# 2_MG32F003_TSSOP20.net
KiCad netlist of a schematic drawn in Altium Designer
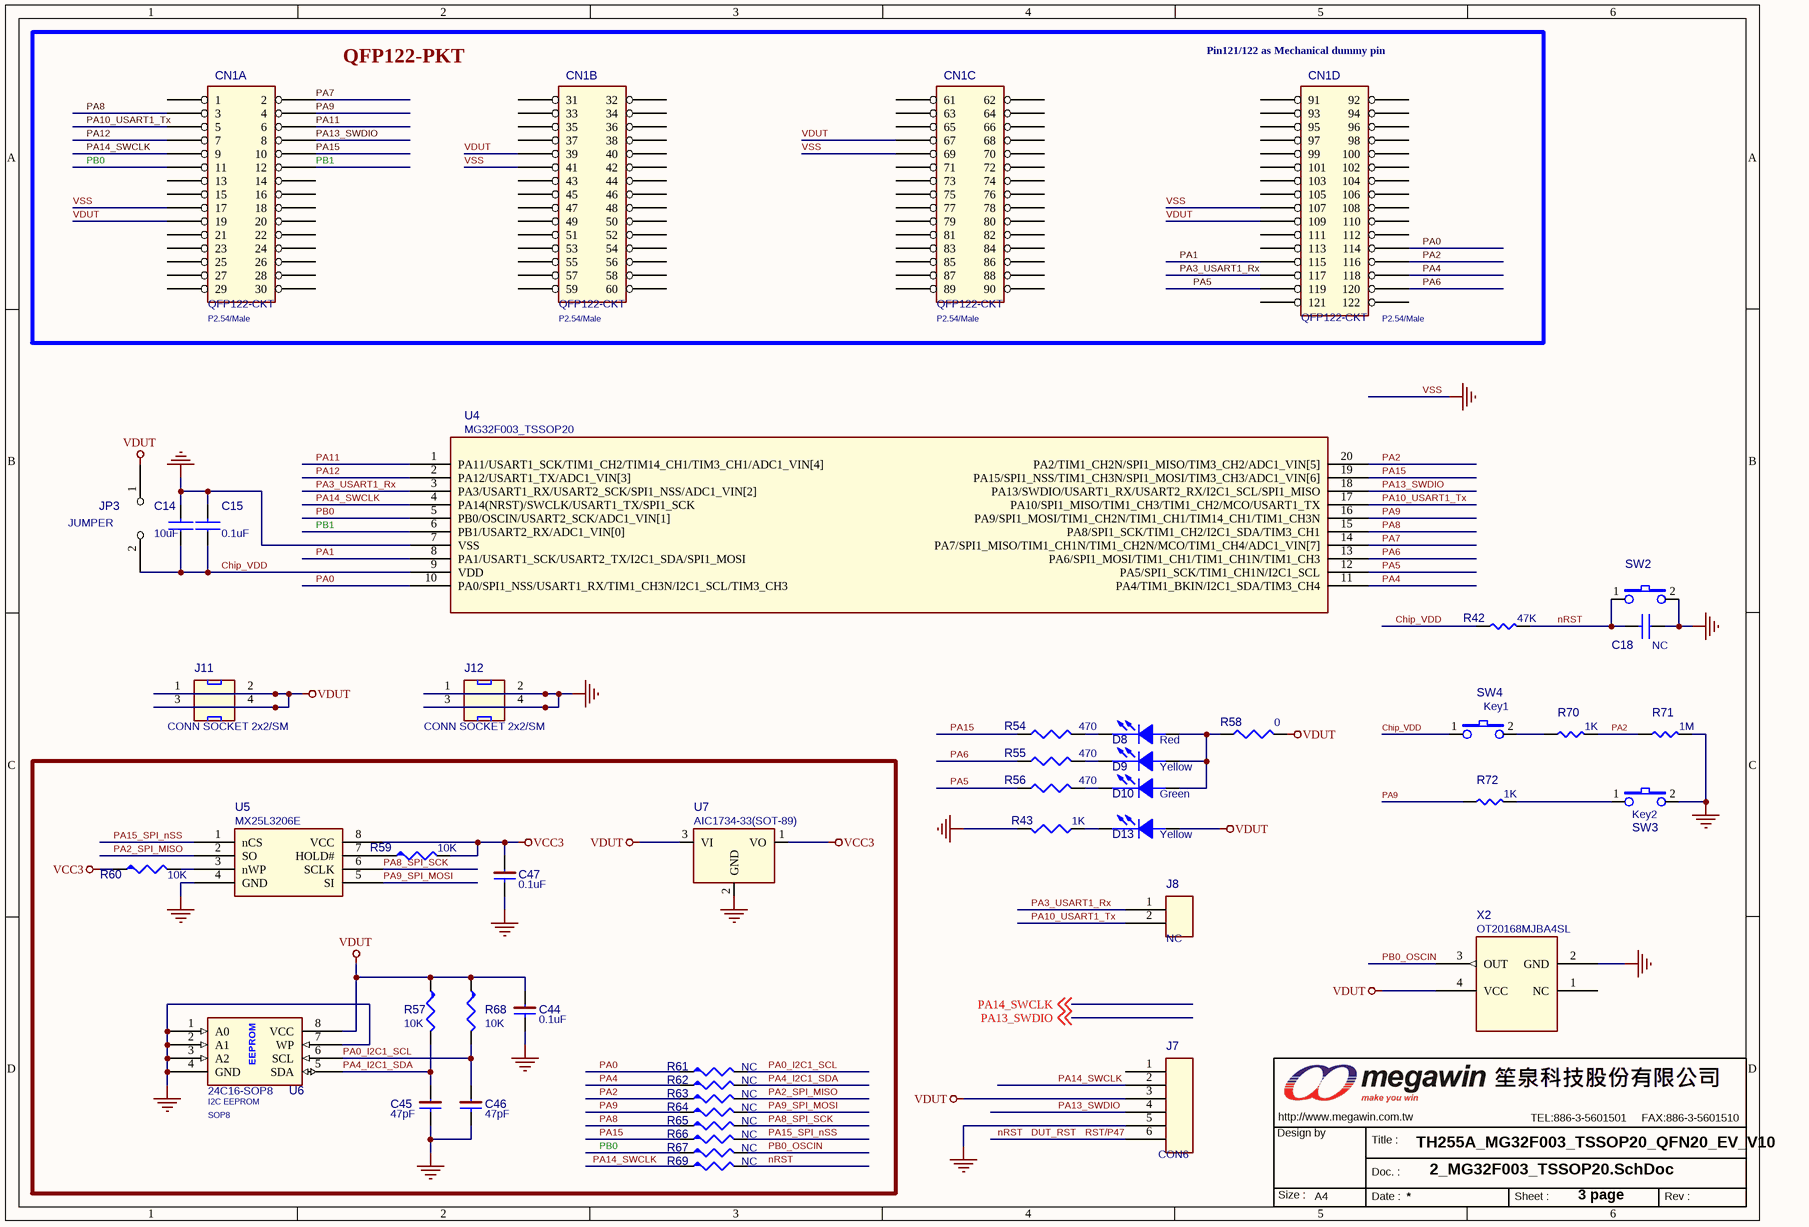
[diagram p0: 2_MG32F003_TSSOP20.SchDoc]

(export (version "E")
  (design (tool "Eeschema 10.0.6"))
  (components
    (comp (ref "C14") (value "10uF") (footprint "C-0603") (libsource (lib "*") (part "CAP NP_Dup1")))
    (comp (ref "C15") (value "0.1uF") (footprint "C-0603") (libsource (lib "*") (part "CAP NP_Dup1")))
    (comp (ref "C18") (value "NC") (footprint "C-0603") (libsource (lib "*") (part "CAP NP_Dup1")))
    (comp (ref "C44") (value "0.1uF") (footprint "C-0603") (libsource (lib "*") (part "CAP-NP")))
    (comp (ref "C45") (value "47pF") (footprint "C-0603") (libsource (lib "*") (part "CAP-NP")))
    (comp (ref "C46") (value "47pF") (footprint "C-0603") (libsource (lib "*") (part "CAP-NP")))
    (comp (ref "C47") (value "0.1uF") (footprint "C-0603") (libsource (lib "*") (part "CAP-NP")))
    (comp (ref "CN1")
      (value "QFP122-CKT")
      (footprint "QFP122-P2.54-CKT")
      (fields (field (name "PACKAGE") "P2.54/Male"))
      (libsource (lib "*") (part "QFP122-CKT"))
    )
    (comp (ref "D8") (value "Red") (libsource (lib "*") (part "LED")))
    (comp (ref "D9") (value "Yellow") (libsource (lib "*") (part "LED")))
    (comp (ref "D10") (value "Green") (libsource (lib "*") (part "LED")))
    (comp (ref "D13") (value "Yellow") (libsource (lib "*") (part "LED")))
    (comp (ref "J7") (value "CON6") (footprint "PS6P254") (libsource (lib "*") (part "CON6_Dup1")))
    (comp (ref "J8") (value "NC") (footprint "PS2P254") (libsource (lib "*") (part "CON2")))
    (comp (ref "J11")
      (value "CONN SOCKET 2x2/SM")
      (footprint "PS2X2P254")
      (libsource (lib "*") (part "CONN SOCKET 2x2/SM"))
    )
    (comp (ref "J12")
      (value "CONN SOCKET 2x2/SM")
      (footprint "PS2X2P254")
      (libsource (lib "*") (part "CONN SOCKET 2x2/SM"))
    )
    (comp (ref "JP3") (value "JUMPER") (footprint "PS2P254") (libsource (lib "*") (part "JUMPER")))
    (comp (ref "MW1")
      (value "MW-A4")
      (footprint "MEGAWIN_3.4")
      (fields
        (field (name "ORGADDR2") "http://www.megawin.com.tw")
        (field (name "ORGADDR3") "TEL:886-3-5601501     FAX:886-3-5601510")
      )
      (libsource (lib "201407_SCHLIB") (part "MW_A4_2"))
    )
    (comp (ref "R42") (value "47K") (footprint "R-0603") (libsource (lib "*") (part "R_Dup3")))
    (comp (ref "R43") (value "1K") (footprint "R-0603") (libsource (lib "*") (part "R_Dup4")))
    (comp (ref "R54") (value "470") (footprint "R-0603") (libsource (lib "*") (part "R_Dup4")))
    (comp (ref "R55") (value "470") (footprint "R-0603") (libsource (lib "*") (part "R_Dup4")))
    (comp (ref "R56") (value "470") (footprint "R-0603") (libsource (lib "*") (part "R_Dup4")))
    (comp (ref "R57") (value "10K") (footprint "R-0603") (libsource (lib "*") (part "R")))
    (comp (ref "R58") (value "0") (footprint "R-0603") (libsource (lib "*") (part "R_Dup4")))
    (comp (ref "R59") (value "10K") (footprint "R-0603") (libsource (lib "*") (part "R")))
    (comp (ref "R60") (value "10K") (footprint "R-0603") (libsource (lib "*") (part "R")))
    (comp (ref "R61") (value "NC") (footprint "R-0603") (libsource (lib "*") (part "R")))
    (comp (ref "R62") (value "NC") (footprint "R-0603") (libsource (lib "*") (part "R")))
    (comp (ref "R63") (value "NC") (footprint "R-0603") (libsource (lib "*") (part "R")))
    (comp (ref "R64") (value "NC") (footprint "R-0603") (libsource (lib "*") (part "R")))
    (comp (ref "R65") (value "NC") (footprint "R-0603") (libsource (lib "*") (part "R")))
    (comp (ref "R66") (value "NC") (footprint "R-0603") (libsource (lib "*") (part "R")))
    (comp (ref "R67") (value "NC") (footprint "R-0603") (libsource (lib "*") (part "R")))
    (comp (ref "R68") (value "10K") (footprint "R-0603") (libsource (lib "*") (part "R")))
    (comp (ref "R69") (value "NC") (footprint "R-0603") (libsource (lib "*") (part "R")))
    (comp (ref "R70") (value "1K") (footprint "R-0603") (libsource (lib "*") (part "R_Dup3")))
    (comp (ref "R71") (value "1M") (footprint "R-0603") (libsource (lib "*") (part "R_Dup3")))
    (comp (ref "R72") (value "1K") (footprint "R-0603") (libsource (lib "*") (part "R_Dup3")))
    (comp (ref "SW2")
      (value "SW TACT-SPST")
      (footprint "SW_T_2P")
      (libsource (lib "*") (part "SW TACT-SPST"))
    )
    (comp (ref "SW3") (value "Key2") (footprint "SW_T_2P") (libsource (lib "*") (part "SW TACT-SPST")))
    (comp (ref "SW4") (value "Key1") (footprint "SW_T_2P") (libsource (lib "*") (part "SW TACT-SPST")))
    (comp (ref "U4")
      (value "MG32F003_TSSOP20")
      (footprint "TSSOP20_170P065")
      (libsource (lib "*") (part "MG32F003_TSSOP20"))
    )
    (comp (ref "U5") (value "MX25L3206E") (footprint "SO8_208P127") (libsource (lib "*") (part "MX25L3206E")))
    (comp (ref "U6")
      (value "24C16-SOP8")
      (footprint "SO8_150P127")
      (fields (field (name "FUNCTION") "I2C EEPROM") (field (name "PACKAGE") "SOP8"))
      (libsource (lib "*") (part "ICM-24CXX"))
    )
    (comp (ref "U7") (value "AIC1734-33(SOT-89)") (libsource (lib "*") (part "AIC1722-33")))
    (comp (ref "X2")
      (value "OT20168MJBA4SL")
      (footprint "OSC_2.0X1.6_SMD")
      (libsource (lib "*") (part "OSC8_0"))
    )
  )
  (nets
    (net (code "1") (name "/Chip_VDD") (class "Default")
      (node (ref "C14") (pin "1") (pinfunction "1_1") (pintype "passive"))
      (node (ref "C15") (pin "1") (pinfunction "1_1") (pintype "passive"))
      (node (ref "JP3") (pin "2") (pinfunction "2_2") (pintype "passive"))
      (node (ref "R42") (pin "1") (pinfunction "1_1") (pintype "passive"))
      (node (ref "SW4") (pin "1") (pinfunction "1_1") (pintype "passive"))
      (node (ref "U4") (pin "9") (pinfunction "VDD_9") (pintype "passive"))
    )
    (net (code "2") (name "/DUT_RST") (class "Default")
      (node (ref "C18") (pin "2") (pinfunction "2_2") (pintype "passive"))
      (node (ref "J7") (pin "6") (pinfunction "6_6") (pintype "passive"))
      (node (ref "R42") (pin "2") (pinfunction "2_2") (pintype "passive"))
      (node (ref "R69") (pin "2") (pinfunction "2_2") (pintype "passive"))
      (node (ref "SW2") (pin "1") (pinfunction "1_1") (pintype "passive"))
    )
    (net (code "3") (name "/PA0") (class "Default")
      (node (ref "CN1") (pin "114") (pinfunction "114_114") (pintype "passive"))
      (node (ref "R61") (pin "1") (pinfunction "1_1") (pintype "passive"))
      (node (ref "U4") (pin "10") (pinfunction "PA0/SPI1_NSS/USART1_RX/TIM1_CH3N/I2C1_SCL/TIM3_CH3_10") (pintype "passive"))
    )
    (net (code "4") (name "/PA0_I2C1_SCL") (class "Default")
      (node (ref "C46") (pin "1") (pinfunction "1_1") (pintype "passive"))
      (node (ref "R61") (pin "2") (pinfunction "2_2") (pintype "passive"))
      (node (ref "R68") (pin "2") (pinfunction "2_2") (pintype "passive"))
      (node (ref "U6") (pin "6") (pinfunction "SCL_6") (pintype "input"))
    )
    (net (code "5") (name "/PA1") (class "Default")
      (node (ref "CN1") (pin "115") (pinfunction "115_115") (pintype "passive"))
      (node (ref "U4") (pin "8") (pinfunction "PA1/USART1_SCK/USART2_TX/I2C1_SDA/SPI1_MOSI_8") (pintype "passive"))
    )
    (net (code "6") (name "/PA2") (class "Default")
      (node (ref "CN1") (pin "116") (pinfunction "116_116") (pintype "passive"))
      (node (ref "R63") (pin "1") (pinfunction "1_1") (pintype "passive"))
      (node (ref "R70") (pin "2") (pinfunction "2_2") (pintype "passive"))
      (node (ref "R71") (pin "1") (pinfunction "1_1") (pintype "passive"))
      (node (ref "U4") (pin "20") (pinfunction "PA2/TIM1_CH2N/SPI1_MISO/TIM3_CH2/ADC1_VIN[5]_20") (pintype "passive"))
    )
    (net (code "7") (name "/PA2_SPI_MISO") (class "Default")
      (node (ref "R63") (pin "2") (pinfunction "2_2") (pintype "passive"))
      (node (ref "U5") (pin "2") (pinfunction "SO_2") (pintype "passive"))
    )
    (net (code "8") (name "/PA3_USART1_Rx") (class "Default")
      (node (ref "CN1") (pin "117") (pinfunction "117_117") (pintype "passive"))
      (node (ref "J8") (pin "1") (pinfunction "1_1") (pintype "passive"))
      (node (ref "U4") (pin "3") (pinfunction "PA3/USART1_RX/USART2_SCK/SPI1_NSS/ADC1_VIN[2]_3") (pintype "passive"))
    )
    (net (code "9") (name "/PA4") (class "Default")
      (node (ref "CN1") (pin "118") (pinfunction "118_118") (pintype "passive"))
      (node (ref "R62") (pin "1") (pinfunction "1_1") (pintype "passive"))
      (node (ref "U4") (pin "11") (pinfunction "PA4/TIM1_BKIN/I2C1_SDA/TIM3_CH4_11") (pintype "passive"))
    )
    (net (code "10") (name "/PA4_I2C1_SDA") (class "Default")
      (node (ref "C45") (pin "1") (pinfunction "1_1") (pintype "passive"))
      (node (ref "R57") (pin "2") (pinfunction "2_2") (pintype "passive"))
      (node (ref "R62") (pin "2") (pinfunction "2_2") (pintype "passive"))
      (node (ref "U6") (pin "5") (pinfunction "SDA_5") (pintype "bidirectional"))
    )
    (net (code "11") (name "/PA5") (class "Default")
      (node (ref "CN1") (pin "119") (pinfunction "119_119") (pintype "passive"))
      (node (ref "R56") (pin "1") (pinfunction "1_1") (pintype "passive"))
      (node (ref "U4") (pin "12") (pinfunction "PA5/SPI1_SCK/TIM1_CH1N/I2C1_SCL_12") (pintype "passive"))
    )
    (net (code "12") (name "/PA6") (class "Default")
      (node (ref "CN1") (pin "120") (pinfunction "120_120") (pintype "passive"))
      (node (ref "R55") (pin "1") (pinfunction "1_1") (pintype "passive"))
      (node (ref "U4") (pin "13") (pinfunction "PA6/SPI1_MOSI/TIM1_CH1/TIM1_CH1N/TIM1_CH3_13") (pintype "passive"))
    )
    (net (code "13") (name "/PA7") (class "Default")
      (node (ref "CN1") (pin "2") (pinfunction "2_2") (pintype "passive"))
      (node (ref "U4") (pin "14") (pinfunction "PA7/SPI1_MISO/TIM1_CH1N/TIM1_CH2N/MCO/TIM1_CH4/ADC1_VIN[7]_14") (pintype "passive"))
    )
    (net (code "14") (name "/PA8") (class "Default")
      (node (ref "CN1") (pin "3") (pinfunction "3_3") (pintype "passive"))
      (node (ref "R65") (pin "1") (pinfunction "1_1") (pintype "passive"))
      (node (ref "U4") (pin "15") (pinfunction "PA8/SPI1_SCK/TIM1_CH2/I2C1_SDA/TIM3_CH1_15") (pintype "passive"))
    )
    (net (code "15") (name "/PA8_SPI_SCK") (class "Default")
      (node (ref "R65") (pin "2") (pinfunction "2_2") (pintype "passive"))
      (node (ref "U5") (pin "6") (pinfunction "SCLK_6") (pintype "passive"))
    )
    (net (code "16") (name "/PA9") (class "Default")
      (node (ref "CN1") (pin "4") (pinfunction "4_4") (pintype "passive"))
      (node (ref "R64") (pin "1") (pinfunction "1_1") (pintype "passive"))
      (node (ref "R72") (pin "1") (pinfunction "1_1") (pintype "passive"))
      (node (ref "U4") (pin "16") (pinfunction "PA9/SPI1_MOSI/TIM1_CH2N/TIM1_CH1/TIM14_CH1/TIM1_CH3N_16") (pintype "passive"))
    )
    (net (code "17") (name "/PA9_SPI_MOSI") (class "Default")
      (node (ref "R64") (pin "2") (pinfunction "2_2") (pintype "passive"))
      (node (ref "U5") (pin "5") (pinfunction "SI_5") (pintype "passive"))
    )
    (net (code "18") (name "/PA10_USART1_Tx") (class "Default")
      (node (ref "CN1") (pin "5") (pinfunction "5_5") (pintype "passive"))
      (node (ref "J8") (pin "2") (pinfunction "2_2") (pintype "passive"))
      (node (ref "U4") (pin "17") (pinfunction "PA10/SPI1_MISO/TIM1_CH3/TIM1_CH2/MCO/USART1_TX_17") (pintype "passive"))
    )
    (net (code "19") (name "/PA11") (class "Default")
      (node (ref "CN1") (pin "6") (pinfunction "6_6") (pintype "passive"))
      (node (ref "U4") (pin "1") (pinfunction "PA11/USART1_SCK/TIM1_CH2/TIM14_CH1/TIM3_CH1/ADC1_VIN[4]_1") (pintype "passive"))
    )
    (net (code "20") (name "/PA12") (class "Default")
      (node (ref "CN1") (pin "7") (pinfunction "7_7") (pintype "passive"))
      (node (ref "U4") (pin "2") (pinfunction "PA12/USART1_TX/ADC1_VIN[3]_2") (pintype "passive"))
    )
    (net (code "21") (name "/PA15") (class "Default")
      (node (ref "CN1") (pin "10") (pinfunction "10_10") (pintype "passive"))
      (node (ref "R54") (pin "1") (pinfunction "1_1") (pintype "passive"))
      (node (ref "R66") (pin "1") (pinfunction "1_1") (pintype "passive"))
      (node (ref "U4") (pin "19") (pinfunction "PA15/SPI1_NSS/TIM1_CH3N/SPI1_MOSI/TIM3_CH3/ADC1_VIN[6]_19") (pintype "passive"))
    )
    (net (code "22") (name "/PA15_SPI_nSS") (class "Default")
      (node (ref "R66") (pin "2") (pinfunction "2_2") (pintype "passive"))
      (node (ref "U5") (pin "1") (pinfunction "nCS_1") (pintype "passive"))
    )
    (net (code "23") (name "/PB0") (class "Default")
      (node (ref "CN1") (pin "11") (pinfunction "11_11") (pintype "passive"))
      (node (ref "R67") (pin "1") (pinfunction "1_1") (pintype "passive"))
      (node (ref "U4") (pin "5") (pinfunction "PB0/OSCIN/USART2_SCK/ADC1_VIN[1]_5") (pintype "passive"))
    )
    (net (code "24") (name "/PB0_OSCIN") (class "Default")
      (node (ref "R67") (pin "2") (pinfunction "2_2") (pintype "passive"))
      (node (ref "X2") (pin "3") (pinfunction "OUT_3") (pintype "output"))
    )
    (net (code "25") (name "/PB1") (class "Default")
      (node (ref "CN1") (pin "12") (pinfunction "12_12") (pintype "passive"))
      (node (ref "U4") (pin "6") (pinfunction "PB1/USART2_RX/ADC1_VIN[0]_6") (pintype "passive"))
    )
    (net (code "26") (name "GND_POWER") (class "Default")
      (node (ref "C14") (pin "2") (pinfunction "2_2") (pintype "passive"))
      (node (ref "C15") (pin "2") (pinfunction "2_2") (pintype "passive"))
      (node (ref "C18") (pin "1") (pinfunction "1_1") (pintype "passive"))
      (node (ref "C44") (pin "2") (pinfunction "2_2") (pintype "passive"))
      (node (ref "C45") (pin "2") (pinfunction "2_2") (pintype "passive"))
      (node (ref "C46") (pin "2") (pinfunction "2_2") (pintype "passive"))
      (node (ref "C47") (pin "2") (pinfunction "2_2") (pintype "passive"))
      (node (ref "CN1") (pin "107") (pinfunction "107_107") (pintype "passive"))
      (node (ref "CN1") (pin "17") (pinfunction "17_17") (pintype "passive"))
      (node (ref "CN1") (pin "41") (pinfunction "41_41") (pintype "passive"))
      (node (ref "CN1") (pin "69") (pinfunction "69_69") (pintype "passive"))
      (node (ref "J12") (pin "1") (pinfunction "1_1") (pintype "passive"))
      (node (ref "J12") (pin "2") (pinfunction "2_2") (pintype "passive"))
      (node (ref "J12") (pin "3") (pinfunction "3_3") (pintype "passive"))
      (node (ref "J12") (pin "4") (pinfunction "4_4") (pintype "passive"))
      (node (ref "J7") (pin "5") (pinfunction "5_5") (pintype "passive"))
      (node (ref "R43") (pin "1") (pinfunction "1_1") (pintype "passive"))
      (node (ref "R71") (pin "2") (pinfunction "2_2") (pintype "passive"))
      (node (ref "SW2") (pin "2") (pinfunction "2_2") (pintype "passive"))
      (node (ref "SW3") (pin "2") (pinfunction "2_2") (pintype "passive"))
      (node (ref "U4") (pin "7") (pinfunction "VSS_7") (pintype "passive"))
      (node (ref "U5") (pin "4") (pinfunction "GND_4") (pintype "passive"))
      (node (ref "U6") (pin "1") (pinfunction "A0_1") (pintype "input"))
      (node (ref "U6") (pin "2") (pinfunction "A1_2") (pintype "input"))
      (node (ref "U6") (pin "3") (pinfunction "A2_3") (pintype "input"))
      (node (ref "U6") (pin "4") (pinfunction "GND_4") (pintype "passive"))
      (node (ref "U6") (pin "7") (pinfunction "WP_7") (pintype "input"))
      (node (ref "U7") (pin "2") (pinfunction "GND_2") (pintype "passive"))
      (node (ref "X2") (pin "2") (pinfunction "GND_2") (pintype "passive"))
    )
    (net (code "27") (name "Net-(D8-CATHODE)") (class "Default")
      (node (ref "D8") (pin "2") (pinfunction "CATHODE_2") (pintype "passive"))
      (node (ref "R54") (pin "2") (pinfunction "2_2") (pintype "passive"))
    )
    (net (code "28") (name "Net-(D9-CATHODE)") (class "Default")
      (node (ref "D9") (pin "2") (pinfunction "CATHODE_2") (pintype "passive"))
      (node (ref "R55") (pin "2") (pinfunction "2_2") (pintype "passive"))
    )
    (net (code "29") (name "Net-(D10-ANODE)") (class "Default")
      (node (ref "D10") (pin "1") (pinfunction "ANODE_1") (pintype "passive"))
      (node (ref "D8") (pin "1") (pinfunction "ANODE_1") (pintype "passive"))
      (node (ref "D9") (pin "1") (pinfunction "ANODE_1") (pintype "passive"))
      (node (ref "R58") (pin "1") (pinfunction "1_1") (pintype "passive"))
    )
    (net (code "30") (name "Net-(D10-CATHODE)") (class "Default")
      (node (ref "D10") (pin "2") (pinfunction "CATHODE_2") (pintype "passive"))
      (node (ref "R56") (pin "2") (pinfunction "2_2") (pintype "passive"))
    )
    (net (code "31") (name "Net-(D13-CATHODE)") (class "Default")
      (node (ref "D13") (pin "2") (pinfunction "CATHODE_2") (pintype "passive"))
      (node (ref "R43") (pin "2") (pinfunction "2_2") (pintype "passive"))
    )
    (net (code "32") (name "Net-(R70-Pad1)") (class "Default")
      (node (ref "R70") (pin "1") (pinfunction "1_1") (pintype "passive"))
      (node (ref "SW4") (pin "2") (pinfunction "2_2") (pintype "passive"))
    )
    (net (code "33") (name "Net-(R72-Pad2)") (class "Default")
      (node (ref "R72") (pin "2") (pinfunction "2_2") (pintype "passive"))
      (node (ref "SW3") (pin "1") (pinfunction "1_1") (pintype "passive"))
    )
    (net (code "34") (name "Net-(U5-HOLD#)") (class "Default")
      (node (ref "R59") (pin "1") (pinfunction "1_1") (pintype "passive"))
      (node (ref "U5") (pin "7") (pinfunction "HOLD#_7") (pintype "passive"))
    )
    (net (code "35") (name "Net-(U5-nWP)") (class "Default")
      (node (ref "R60") (pin "2") (pinfunction "2_2") (pintype "passive"))
      (node (ref "U5") (pin "3") (pinfunction "nWP_3") (pintype "passive"))
    )
    (net (code "36") (name "PA13_SWDIO") (class "Default")
      (node (ref "CN1") (pin "8") (pinfunction "8_8") (pintype "passive"))
      (node (ref "J7") (pin "4") (pinfunction "4_4") (pintype "passive"))
      (node (ref "U4") (pin "18") (pinfunction "PA13/SWDIO/USART1_RX/USART2_RX/I2C1_SCL/SPI1_MISO_18") (pintype "passive"))
    )
    (net (code "37") (name "PA14_SWCLK") (class "Default")
      (node (ref "CN1") (pin "9") (pinfunction "9_9") (pintype "passive"))
      (node (ref "J7") (pin "2") (pinfunction "2_2") (pintype "passive"))
      (node (ref "R69") (pin "1") (pinfunction "1_1") (pintype "passive"))
      (node (ref "U4") (pin "4") (pinfunction "PA14(NRST)/SWCLK/USART1_TX/SPI1_SCK_4") (pintype "passive"))
    )
    (net (code "38") (name "VCC3") (class "Default")
      (node (ref "C47") (pin "1") (pinfunction "1_1") (pintype "passive"))
      (node (ref "R59") (pin "2") (pinfunction "2_2") (pintype "passive"))
      (node (ref "R60") (pin "1") (pinfunction "1_1") (pintype "passive"))
      (node (ref "U5") (pin "8") (pinfunction "VCC_8") (pintype "passive"))
      (node (ref "U7") (pin "1") (pinfunction "VO_1") (pintype "passive"))
    )
    (net (code "39") (name "VDUT") (class "Default")
      (node (ref "C44") (pin "1") (pinfunction "1_1") (pintype "passive"))
      (node (ref "CN1") (pin "109") (pinfunction "109_109") (pintype "passive"))
      (node (ref "CN1") (pin "19") (pinfunction "19_19") (pintype "passive"))
      (node (ref "CN1") (pin "39") (pinfunction "39_39") (pintype "passive"))
      (node (ref "CN1") (pin "67") (pinfunction "67_67") (pintype "passive"))
      (node (ref "D13") (pin "1") (pinfunction "ANODE_1") (pintype "passive"))
      (node (ref "J11") (pin "1") (pinfunction "1_1") (pintype "passive"))
      (node (ref "J11") (pin "2") (pinfunction "2_2") (pintype "passive"))
      (node (ref "J11") (pin "3") (pinfunction "3_3") (pintype "passive"))
      (node (ref "J11") (pin "4") (pinfunction "4_4") (pintype "passive"))
      (node (ref "J7") (pin "3") (pinfunction "3_3") (pintype "passive"))
      (node (ref "JP3") (pin "1") (pinfunction "1_1") (pintype "passive"))
      (node (ref "R57") (pin "1") (pinfunction "1_1") (pintype "passive"))
      (node (ref "R58") (pin "2") (pinfunction "2_2") (pintype "passive"))
      (node (ref "R68") (pin "1") (pinfunction "1_1") (pintype "passive"))
      (node (ref "U6") (pin "8") (pinfunction "VCC_8") (pintype "passive"))
      (node (ref "U7") (pin "3") (pinfunction "VI_3") (pintype "passive"))
      (node (ref "X2") (pin "4") (pinfunction "VCC_4") (pintype "passive"))
    )
    (net (code "40") (name "unconnected-(CN1-Pad1)") (class "Default")
      (node (ref "CN1") (pin "1") (pinfunction "1_1") (pintype "passive"))
    )
    (net (code "41") (name "unconnected-(CN1-Pad13)") (class "Default")
      (node (ref "CN1") (pin "13") (pinfunction "13_13") (pintype "passive"))
    )
    (net (code "42") (name "unconnected-(CN1-Pad14)") (class "Default")
      (node (ref "CN1") (pin "14") (pinfunction "14_14") (pintype "passive"))
    )
    (net (code "43") (name "unconnected-(CN1-Pad15)") (class "Default")
      (node (ref "CN1") (pin "15") (pinfunction "15_15") (pintype "passive"))
    )
    (net (code "44") (name "unconnected-(CN1-Pad16)") (class "Default")
      (node (ref "CN1") (pin "16") (pinfunction "16_16") (pintype "passive"))
    )
    (net (code "45") (name "unconnected-(CN1-Pad18)") (class "Default")
      (node (ref "CN1") (pin "18") (pinfunction "18_18") (pintype "passive"))
    )
    (net (code "46") (name "unconnected-(CN1-Pad20)") (class "Default")
      (node (ref "CN1") (pin "20") (pinfunction "20_20") (pintype "passive"))
    )
    (net (code "47") (name "unconnected-(CN1-Pad21)") (class "Default")
      (node (ref "CN1") (pin "21") (pinfunction "21_21") (pintype "passive"))
    )
    (net (code "48") (name "unconnected-(CN1-Pad22)") (class "Default")
      (node (ref "CN1") (pin "22") (pinfunction "22_22") (pintype "passive"))
    )
    (net (code "49") (name "unconnected-(CN1-Pad23)") (class "Default")
      (node (ref "CN1") (pin "23") (pinfunction "23_23") (pintype "passive"))
    )
    (net (code "50") (name "unconnected-(CN1-Pad24)") (class "Default")
      (node (ref "CN1") (pin "24") (pinfunction "24_24") (pintype "passive"))
    )
    (net (code "51") (name "unconnected-(CN1-Pad25)") (class "Default")
      (node (ref "CN1") (pin "25") (pinfunction "25_25") (pintype "passive"))
    )
    (net (code "52") (name "unconnected-(CN1-Pad26)") (class "Default")
      (node (ref "CN1") (pin "26") (pinfunction "26_26") (pintype "passive"))
    )
    (net (code "53") (name "unconnected-(CN1-Pad27)") (class "Default")
      (node (ref "CN1") (pin "27") (pinfunction "27_27") (pintype "passive"))
    )
    (net (code "54") (name "unconnected-(CN1-Pad28)") (class "Default")
      (node (ref "CN1") (pin "28") (pinfunction "28_28") (pintype "passive"))
    )
    (net (code "55") (name "unconnected-(CN1-Pad29)") (class "Default")
      (node (ref "CN1") (pin "29") (pinfunction "29_29") (pintype "passive"))
    )
    (net (code "56") (name "unconnected-(CN1-Pad30)") (class "Default")
      (node (ref "CN1") (pin "30") (pinfunction "30_30") (pintype "passive"))
    )
    (net (code "57") (name "unconnected-(CN1-Pad31)") (class "Default")
      (node (ref "CN1") (pin "31") (pinfunction "31_31") (pintype "passive"))
    )
    (net (code "58") (name "unconnected-(CN1-Pad32)") (class "Default")
      (node (ref "CN1") (pin "32") (pinfunction "32_32") (pintype "passive"))
    )
    (net (code "59") (name "unconnected-(CN1-Pad33)") (class "Default")
      (node (ref "CN1") (pin "33") (pinfunction "33_33") (pintype "passive"))
    )
    (net (code "60") (name "unconnected-(CN1-Pad34)") (class "Default")
      (node (ref "CN1") (pin "34") (pinfunction "34_34") (pintype "passive"))
    )
    (net (code "61") (name "unconnected-(CN1-Pad35)") (class "Default")
      (node (ref "CN1") (pin "35") (pinfunction "35_35") (pintype "passive"))
    )
    (net (code "62") (name "unconnected-(CN1-Pad36)") (class "Default")
      (node (ref "CN1") (pin "36") (pinfunction "36_36") (pintype "passive"))
    )
    (net (code "63") (name "unconnected-(CN1-Pad37)") (class "Default")
      (node (ref "CN1") (pin "37") (pinfunction "37_37") (pintype "passive"))
    )
    (net (code "64") (name "unconnected-(CN1-Pad38)") (class "Default")
      (node (ref "CN1") (pin "38") (pinfunction "38_38") (pintype "passive"))
    )
    (net (code "65") (name "unconnected-(CN1-Pad40)") (class "Default")
      (node (ref "CN1") (pin "40") (pinfunction "40_40") (pintype "passive"))
    )
    (net (code "66") (name "unconnected-(CN1-Pad42)") (class "Default")
      (node (ref "CN1") (pin "42") (pinfunction "42_42") (pintype "passive"))
    )
    (net (code "67") (name "unconnected-(CN1-Pad43)") (class "Default")
      (node (ref "CN1") (pin "43") (pinfunction "43_43") (pintype "passive"))
    )
    (net (code "68") (name "unconnected-(CN1-Pad44)") (class "Default")
      (node (ref "CN1") (pin "44") (pinfunction "44_44") (pintype "passive"))
    )
    (net (code "69") (name "unconnected-(CN1-Pad45)") (class "Default")
      (node (ref "CN1") (pin "45") (pinfunction "45_45") (pintype "passive"))
    )
    (net (code "70") (name "unconnected-(CN1-Pad46)") (class "Default")
      (node (ref "CN1") (pin "46") (pinfunction "46_46") (pintype "passive"))
    )
    (net (code "71") (name "unconnected-(CN1-Pad47)") (class "Default")
      (node (ref "CN1") (pin "47") (pinfunction "47_47") (pintype "passive"))
    )
    (net (code "72") (name "unconnected-(CN1-Pad48)") (class "Default")
      (node (ref "CN1") (pin "48") (pinfunction "48_48") (pintype "passive"))
    )
    (net (code "73") (name "unconnected-(CN1-Pad49)") (class "Default")
      (node (ref "CN1") (pin "49") (pinfunction "49_49") (pintype "passive"))
    )
    (net (code "74") (name "unconnected-(CN1-Pad50)") (class "Default")
      (node (ref "CN1") (pin "50") (pinfunction "50_50") (pintype "passive"))
    )
    (net (code "75") (name "unconnected-(CN1-Pad51)") (class "Default")
      (node (ref "CN1") (pin "51") (pinfunction "51_51") (pintype "passive"))
    )
    (net (code "76") (name "unconnected-(CN1-Pad52)") (class "Default")
      (node (ref "CN1") (pin "52") (pinfunction "52_52") (pintype "passive"))
    )
    (net (code "77") (name "unconnected-(CN1-Pad53)") (class "Default")
      (node (ref "CN1") (pin "53") (pinfunction "53_53") (pintype "passive"))
    )
    (net (code "78") (name "unconnected-(CN1-Pad54)") (class "Default")
      (node (ref "CN1") (pin "54") (pinfunction "54_54") (pintype "passive"))
    )
    (net (code "79") (name "unconnected-(CN1-Pad55)") (class "Default")
      (node (ref "CN1") (pin "55") (pinfunction "55_55") (pintype "passive"))
    )
    (net (code "80") (name "unconnected-(CN1-Pad56)") (class "Default")
      (node (ref "CN1") (pin "56") (pinfunction "56_56") (pintype "passive"))
    )
    (net (code "81") (name "unconnected-(CN1-Pad57)") (class "Default")
      (node (ref "CN1") (pin "57") (pinfunction "57_57") (pintype "passive"))
    )
    (net (code "82") (name "unconnected-(CN1-Pad58)") (class "Default")
      (node (ref "CN1") (pin "58") (pinfunction "58_58") (pintype "passive"))
    )
    (net (code "83") (name "unconnected-(CN1-Pad59)") (class "Default")
      (node (ref "CN1") (pin "59") (pinfunction "59_59") (pintype "passive"))
    )
    (net (code "84") (name "unconnected-(CN1-Pad60)") (class "Default")
      (node (ref "CN1") (pin "60") (pinfunction "60_60") (pintype "passive"))
    )
    (net (code "85") (name "unconnected-(CN1-Pad61)") (class "Default")
      (node (ref "CN1") (pin "61") (pinfunction "61_61") (pintype "passive"))
    )
    (net (code "86") (name "unconnected-(CN1-Pad62)") (class "Default")
      (node (ref "CN1") (pin "62") (pinfunction "62_62") (pintype "passive"))
    )
    (net (code "87") (name "unconnected-(CN1-Pad63)") (class "Default")
      (node (ref "CN1") (pin "63") (pinfunction "63_63") (pintype "passive"))
    )
    (net (code "88") (name "unconnected-(CN1-Pad64)") (class "Default")
      (node (ref "CN1") (pin "64") (pinfunction "64_64") (pintype "passive"))
    )
    (net (code "89") (name "unconnected-(CN1-Pad65)") (class "Default")
      (node (ref "CN1") (pin "65") (pinfunction "65_65") (pintype "passive"))
    )
    (net (code "90") (name "unconnected-(CN1-Pad66)") (class "Default")
      (node (ref "CN1") (pin "66") (pinfunction "66_66") (pintype "passive"))
    )
    (net (code "91") (name "unconnected-(CN1-Pad68)") (class "Default")
      (node (ref "CN1") (pin "68") (pinfunction "68_68") (pintype "passive"))
    )
    (net (code "92") (name "unconnected-(CN1-Pad70)") (class "Default")
      (node (ref "CN1") (pin "70") (pinfunction "70_70") (pintype "passive"))
    )
    (net (code "93") (name "unconnected-(CN1-Pad71)") (class "Default")
      (node (ref "CN1") (pin "71") (pinfunction "71_71") (pintype "passive"))
    )
    (net (code "94") (name "unconnected-(CN1-Pad72)") (class "Default")
      (node (ref "CN1") (pin "72") (pinfunction "72_72") (pintype "passive"))
    )
    (net (code "95") (name "unconnected-(CN1-Pad73)") (class "Default")
      (node (ref "CN1") (pin "73") (pinfunction "73_73") (pintype "passive"))
    )
    (net (code "96") (name "unconnected-(CN1-Pad74)") (class "Default")
      (node (ref "CN1") (pin "74") (pinfunction "74_74") (pintype "passive"))
    )
    (net (code "97") (name "unconnected-(CN1-Pad75)") (class "Default")
      (node (ref "CN1") (pin "75") (pinfunction "75_75") (pintype "passive"))
    )
    (net (code "98") (name "unconnected-(CN1-Pad76)") (class "Default")
      (node (ref "CN1") (pin "76") (pinfunction "76_76") (pintype "passive"))
    )
    (net (code "99") (name "unconnected-(CN1-Pad77)") (class "Default")
      (node (ref "CN1") (pin "77") (pinfunction "77_77") (pintype "passive"))
    )
    (net (code "100") (name "unconnected-(CN1-Pad78)") (class "Default")
      (node (ref "CN1") (pin "78") (pinfunction "78_78") (pintype "passive"))
    )
    (net (code "101") (name "unconnected-(CN1-Pad79)") (class "Default")
      (node (ref "CN1") (pin "79") (pinfunction "79_79") (pintype "passive"))
    )
    (net (code "102") (name "unconnected-(CN1-Pad80)") (class "Default")
      (node (ref "CN1") (pin "80") (pinfunction "80_80") (pintype "passive"))
    )
    (net (code "103") (name "unconnected-(CN1-Pad81)") (class "Default")
      (node (ref "CN1") (pin "81") (pinfunction "81_81") (pintype "passive"))
    )
    (net (code "104") (name "unconnected-(CN1-Pad82)") (class "Default")
      (node (ref "CN1") (pin "82") (pinfunction "82_82") (pintype "passive"))
    )
    (net (code "105") (name "unconnected-(CN1-Pad83)") (class "Default")
      (node (ref "CN1") (pin "83") (pinfunction "83_83") (pintype "passive"))
    )
    (net (code "106") (name "unconnected-(CN1-Pad84)") (class "Default")
      (node (ref "CN1") (pin "84") (pinfunction "84_84") (pintype "passive"))
    )
    (net (code "107") (name "unconnected-(CN1-Pad85)") (class "Default")
      (node (ref "CN1") (pin "85") (pinfunction "85_85") (pintype "passive"))
    )
    (net (code "108") (name "unconnected-(CN1-Pad86)") (class "Default")
      (node (ref "CN1") (pin "86") (pinfunction "86_86") (pintype "passive"))
    )
    (net (code "109") (name "unconnected-(CN1-Pad87)") (class "Default")
      (node (ref "CN1") (pin "87") (pinfunction "87_87") (pintype "passive"))
    )
    (net (code "110") (name "unconnected-(CN1-Pad88)") (class "Default")
      (node (ref "CN1") (pin "88") (pinfunction "88_88") (pintype "passive"))
    )
    (net (code "111") (name "unconnected-(CN1-Pad89)") (class "Default")
      (node (ref "CN1") (pin "89") (pinfunction "89_89") (pintype "passive"))
    )
    (net (code "112") (name "unconnected-(CN1-Pad90)") (class "Default")
      (node (ref "CN1") (pin "90") (pinfunction "90_90") (pintype "passive"))
    )
    (net (code "113") (name "unconnected-(CN1-Pad91)") (class "Default")
      (node (ref "CN1") (pin "91") (pinfunction "91_91") (pintype "passive"))
    )
    (net (code "114") (name "unconnected-(CN1-Pad92)") (class "Default")
      (node (ref "CN1") (pin "92") (pinfunction "92_92") (pintype "passive"))
    )
    (net (code "115") (name "unconnected-(CN1-Pad93)") (class "Default")
      (node (ref "CN1") (pin "93") (pinfunction "93_93") (pintype "passive"))
    )
    (net (code "116") (name "unconnected-(CN1-Pad94)") (class "Default")
      (node (ref "CN1") (pin "94") (pinfunction "94_94") (pintype "passive"))
    )
    (net (code "117") (name "unconnected-(CN1-Pad95)") (class "Default")
      (node (ref "CN1") (pin "95") (pinfunction "95_95") (pintype "passive"))
    )
    (net (code "118") (name "unconnected-(CN1-Pad96)") (class "Default")
      (node (ref "CN1") (pin "96") (pinfunction "96_96") (pintype "passive"))
    )
    (net (code "119") (name "unconnected-(CN1-Pad97)") (class "Default")
      (node (ref "CN1") (pin "97") (pinfunction "97_97") (pintype "passive"))
    )
    (net (code "120") (name "unconnected-(CN1-Pad98)") (class "Default")
      (node (ref "CN1") (pin "98") (pinfunction "98_98") (pintype "passive"))
    )
    (net (code "121") (name "unconnected-(CN1-Pad99)") (class "Default")
      (node (ref "CN1") (pin "99") (pinfunction "99_99") (pintype "passive"))
    )
    (net (code "122") (name "unconnected-(CN1-Pad100)") (class "Default")
      (node (ref "CN1") (pin "100") (pinfunction "100_100") (pintype "passive"))
    )
    (net (code "123") (name "unconnected-(CN1-Pad101)") (class "Default")
      (node (ref "CN1") (pin "101") (pinfunction "101_101") (pintype "passive"))
    )
    (net (code "124") (name "unconnected-(CN1-Pad102)") (class "Default")
      (node (ref "CN1") (pin "102") (pinfunction "102_102") (pintype "passive"))
    )
    (net (code "125") (name "unconnected-(CN1-Pad103)") (class "Default")
      (node (ref "CN1") (pin "103") (pinfunction "103_103") (pintype "passive"))
    )
    (net (code "126") (name "unconnected-(CN1-Pad104)") (class "Default")
      (node (ref "CN1") (pin "104") (pinfunction "104_104") (pintype "passive"))
    )
    (net (code "127") (name "unconnected-(CN1-Pad105)") (class "Default")
      (node (ref "CN1") (pin "105") (pinfunction "105_105") (pintype "passive"))
    )
    (net (code "128") (name "unconnected-(CN1-Pad106)") (class "Default")
      (node (ref "CN1") (pin "106") (pinfunction "106_106") (pintype "passive"))
    )
    (net (code "129") (name "unconnected-(CN1-Pad108)") (class "Default")
      (node (ref "CN1") (pin "108") (pinfunction "108_108") (pintype "passive"))
    )
    (net (code "130") (name "unconnected-(CN1-Pad110)") (class "Default")
      (node (ref "CN1") (pin "110") (pinfunction "110_110") (pintype "passive"))
    )
    (net (code "131") (name "unconnected-(CN1-Pad111)") (class "Default")
      (node (ref "CN1") (pin "111") (pinfunction "111_111") (pintype "passive"))
    )
    (net (code "132") (name "unconnected-(CN1-Pad112)") (class "Default")
      (node (ref "CN1") (pin "112") (pinfunction "112_112") (pintype "passive"))
    )
    (net (code "133") (name "unconnected-(CN1-Pad113)") (class "Default")
      (node (ref "CN1") (pin "113") (pinfunction "113_113") (pintype "passive"))
    )
    (net (code "134") (name "unconnected-(CN1-Pad121)") (class "Default")
      (node (ref "CN1") (pin "121") (pinfunction "121_121") (pintype "passive"))
    )
    (net (code "135") (name "unconnected-(CN1-Pad122)") (class "Default")
      (node (ref "CN1") (pin "122") (pinfunction "122_122") (pintype "passive"))
    )
    (net (code "136") (name "unconnected-(J7-Pad1)") (class "Default")
      (node (ref "J7") (pin "1") (pinfunction "1_1") (pintype "passive"))
    )
    (net (code "137") (name "unconnected-(X2-NC-Pad1)") (class "Default")
      (node (ref "X2") (pin "1") (pinfunction "NC_1") (pintype "passive"))
    )
  )
)
